# Quad_circuit_Dejun_Ryan.net
KiCad netlist of a schematic drawn in EAGLE
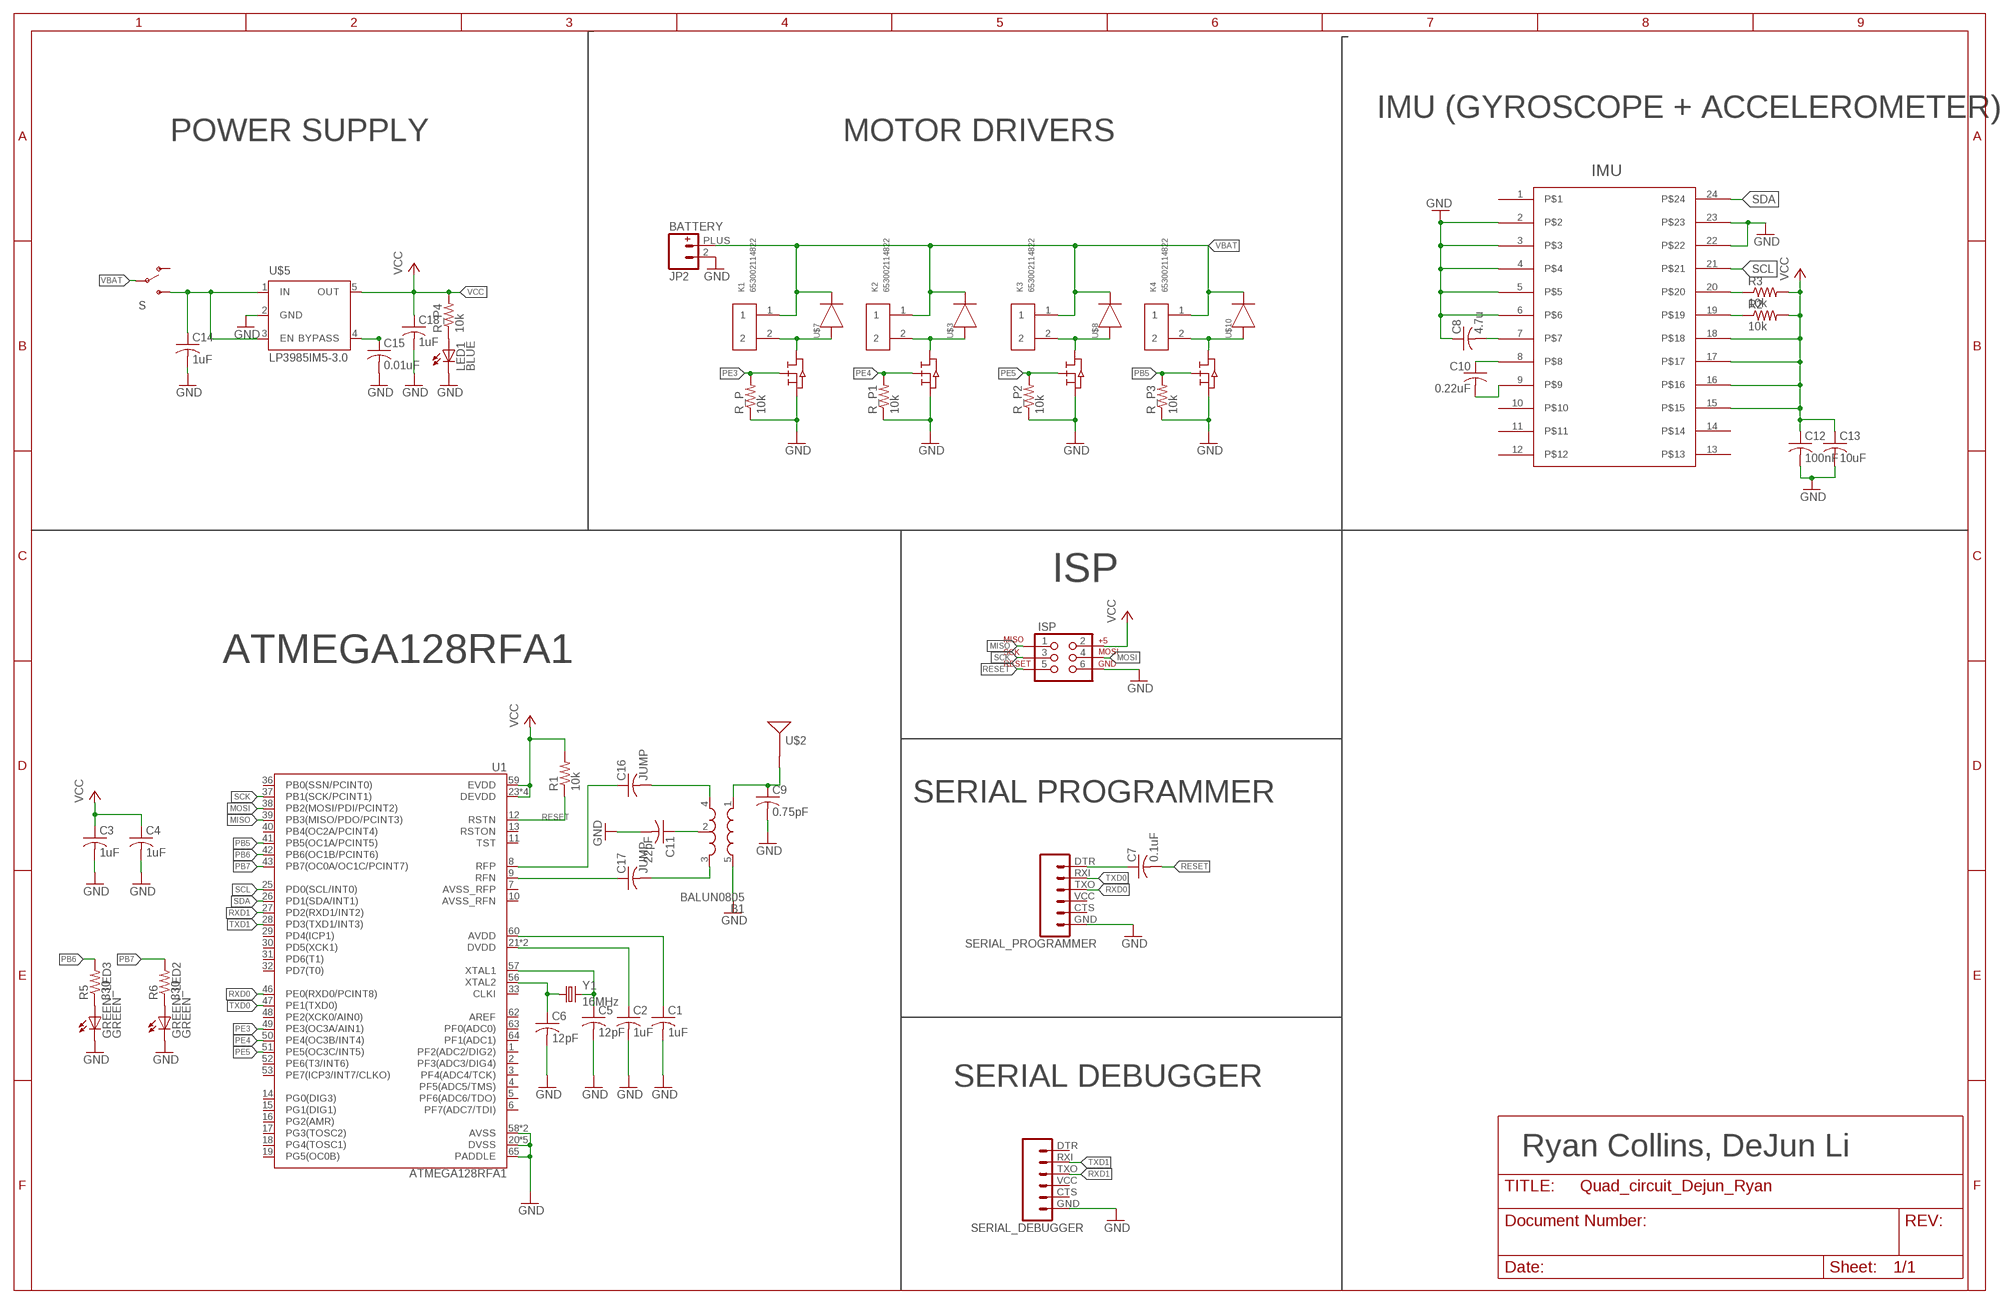
[diagram p0: schematic, sheet 1]

(export (version "E")
  (design (tool "Eeschema 10.0.6"))
  (components
    (comp (ref "B1")
      (value "BALUN0805")
      (footprint "eagle-import:BALUN")
      (libsource (lib "eagle-import") (part "BALUN0805"))
    )
    (comp (ref "C1")
      (value "1uF")
      (footprint "eagle-import:C0805")
      (libsource (lib "eagle-import") (part "C-USC0805"))
    )
    (comp (ref "C2")
      (value "1uF")
      (footprint "eagle-import:C0805")
      (libsource (lib "eagle-import") (part "C-USC0805"))
    )
    (comp (ref "C3")
      (value "1uF")
      (footprint "eagle-import:C0805")
      (libsource (lib "eagle-import") (part "C-USC0805"))
    )
    (comp (ref "C4")
      (value "1uF")
      (footprint "eagle-import:C0805")
      (libsource (lib "eagle-import") (part "C-USC0805"))
    )
    (comp (ref "C5")
      (value "12pF")
      (footprint "eagle-import:C0805")
      (libsource (lib "eagle-import") (part "C-USC0805"))
    )
    (comp (ref "C6")
      (value "12pF")
      (footprint "eagle-import:C0805")
      (libsource (lib "eagle-import") (part "C-USC0805"))
    )
    (comp (ref "C7")
      (value "0.1uF")
      (footprint "eagle-import:C0805")
      (libsource (lib "eagle-import") (part "C-USC0805"))
    )
    (comp (ref "C8")
      (value "4.7u")
      (footprint "eagle-import:C0805")
      (libsource (lib "eagle-import") (part "C-USC0805"))
    )
    (comp (ref "C9")
      (value "0.75pF")
      (footprint "eagle-import:C0805")
      (libsource (lib "eagle-import") (part "C-USC0805"))
    )
    (comp (ref "C10")
      (value "0.22uF")
      (footprint "eagle-import:C0805")
      (libsource (lib "eagle-import") (part "C-USC0805"))
    )
    (comp (ref "C11")
      (value "22pF")
      (footprint "eagle-import:C0805")
      (libsource (lib "eagle-import") (part "C-USC0805"))
    )
    (comp (ref "C12")
      (value "100nF")
      (footprint "eagle-import:C0805")
      (libsource (lib "eagle-import") (part "C-USC0805"))
    )
    (comp (ref "C13")
      (value "10uF")
      (footprint "eagle-import:C0805")
      (libsource (lib "eagle-import") (part "C-USC0805"))
    )
    (comp (ref "C14")
      (value "1uF")
      (footprint "eagle-import:C0805")
      (libsource (lib "eagle-import") (part "C-USC0805"))
    )
    (comp (ref "C15")
      (value "0.01uF")
      (footprint "eagle-import:C0805")
      (libsource (lib "eagle-import") (part "C-USC0805"))
    )
    (comp (ref "C16")
      (value "JUMP")
      (footprint "eagle-import:C0805")
      (libsource (lib "eagle-import") (part "C-USC0805"))
    )
    (comp (ref "C17")
      (value "JUMP")
      (footprint "eagle-import:C0805")
      (libsource (lib "eagle-import") (part "C-USC0805"))
    )
    (comp (ref "C18")
      (value "1uF")
      (footprint "eagle-import:C0805")
      (libsource (lib "eagle-import") (part "C-USC0805"))
    )
    (comp (ref "GREEN_LED2")
      (value "GREEN")
      (footprint "eagle-import:CHIP-LED0805")
      (libsource (lib "eagle-import") (part "LEDCHIP-LED0805"))
    )
    (comp (ref "GREEN_LED3")
      (value "GREEN")
      (footprint "eagle-import:CHIP-LED0805")
      (libsource (lib "eagle-import") (part "LEDCHIP-LED0805"))
    )
    (comp (ref "IMU")
      (value "IMU_LSM9DS0")
      (footprint "eagle-import:IMU_LSM9DS0")
      (libsource (lib "eagle-import") (part "IMU_LSM9DS0"))
    )
    (comp (ref "ISP")
      (value "AVR_SPI_PRG_6NS")
      (footprint "eagle-import:2X3-NS")
      (libsource (lib "eagle-import") (part "AVR_SPI_PRG_6NS"))
    )
    (comp (ref "JP2")
      (value "BATTERY")
      (footprint "eagle-import:1X02")
      (libsource (lib "eagle-import") (part "M02PTH"))
    )
    (comp (ref "K1")
      (value "653002114822")
      (footprint "eagle-import:653002114822")
      (libsource (lib "eagle-import") (part "653002114822"))
    )
    (comp (ref "K2")
      (value "653002114822")
      (footprint "eagle-import:653002114822")
      (libsource (lib "eagle-import") (part "653002114822"))
    )
    (comp (ref "K3")
      (value "653002114822")
      (footprint "eagle-import:653002114822")
      (libsource (lib "eagle-import") (part "653002114822"))
    )
    (comp (ref "K4")
      (value "653002114822")
      (footprint "eagle-import:653002114822")
      (libsource (lib "eagle-import") (part "653002114822"))
    )
    (comp (ref "LED1")
      (value "BLUE")
      (footprint "eagle-import:CHIP-LED0805")
      (libsource (lib "eagle-import") (part "LEDCHIP-LED0805"))
    )
    (comp (ref "R1")
      (value "10k")
      (footprint "eagle-import:R0805")
      (libsource (lib "eagle-import") (part "R-US_R0805"))
    )
    (comp (ref "R2")
      (value "10k")
      (footprint "eagle-import:R0805")
      (libsource (lib "eagle-import") (part "R-US_R0805"))
    )
    (comp (ref "R3")
      (value "10k")
      (footprint "eagle-import:R0805")
      (libsource (lib "eagle-import") (part "R-US_R0805"))
    )
    (comp (ref "R5")
      (value "330")
      (footprint "eagle-import:R0805")
      (libsource (lib "eagle-import") (part "R-US_R0805"))
    )
    (comp (ref "R6")
      (value "330")
      (footprint "eagle-import:R0805")
      (libsource (lib "eagle-import") (part "R-US_R0805"))
    )
    (comp (ref "R_P")
      (value "10k")
      (footprint "eagle-import:R0805")
      (libsource (lib "eagle-import") (part "R-US_R0805"))
    )
    (comp (ref "R_P1")
      (value "10k")
      (footprint "eagle-import:R0805")
      (libsource (lib "eagle-import") (part "R-US_R0805"))
    )
    (comp (ref "R_P2")
      (value "10k")
      (footprint "eagle-import:R0805")
      (libsource (lib "eagle-import") (part "R-US_R0805"))
    )
    (comp (ref "R_P3")
      (value "10k")
      (footprint "eagle-import:R0805")
      (libsource (lib "eagle-import") (part "R-US_R0805"))
    )
    (comp (ref "R_P4")
      (value "10k")
      (footprint "eagle-import:R0805")
      (libsource (lib "eagle-import") (part "R-US_R0805"))
    )
    (comp (ref "S")
      (value "WEEEEEE")
      (footprint "eagle-import:SWITCH-SPDT")
      (libsource (lib "eagle-import") (part "SWITCH-SPDTPTH"))
    )
    (comp (ref "SERIAL_DEBUGGER")
      (value "FTDI_BASICPTH")
      (footprint "eagle-import:FTDI_BASIC")
      (libsource (lib "eagle-import") (part "FTDI_BASICPTH"))
    )
    (comp (ref "SERIAL_PROGRAMMER")
      (value "FTDI_BASICPTH")
      (footprint "eagle-import:FTDI_BASIC")
      (libsource (lib "eagle-import") (part "FTDI_BASICPTH"))
    )
    (comp (ref "U$1")
      (value "MOSFET-SI2302CDS")
      (footprint "eagle-import:MOSFET-SI2302CDS")
      (fields (field (name "CREATOR") "DEJUN"))
      (libsource (lib "eagle-import") (part "MOSFET-SI2302CDS"))
    )
    (comp (ref "U$2")
      (value "ANTENNA2SMD5")
      (footprint "eagle-import:ANTENNA-CHIP5")
      (libsource (lib "eagle-import") (part "ANTENNA2SMD5"))
    )
    (comp (ref "U$3")
      (value "DIODE")
      (footprint "eagle-import:DIODE-BAS16WS")
      (fields (field (name "CREATOR") "DEJUN"))
      (libsource (lib "eagle-import") (part "DIODE-BAS16WS"))
    )
    (comp (ref "U$4")
      (value "MOSFET-SI2302CDS")
      (footprint "eagle-import:MOSFET-SI2302CDS")
      (fields (field (name "CREATOR") "DEJUN"))
      (libsource (lib "eagle-import") (part "MOSFET-SI2302CDS"))
    )
    (comp (ref "U$5")
      (value "LP3985IM5-3.0")
      (footprint "eagle-import:SOT23-DBV")
      (libsource (lib "eagle-import") (part "LP3985IM5-3.0"))
    )
    (comp (ref "U$6")
      (value "MOSFET-SI2302CDS")
      (footprint "eagle-import:MOSFET-SI2302CDS")
      (fields (field (name "CREATOR") "DEJUN"))
      (libsource (lib "eagle-import") (part "MOSFET-SI2302CDS"))
    )
    (comp (ref "U$7")
      (value "DIODE")
      (footprint "eagle-import:DIODE-BAS16WS")
      (fields (field (name "CREATOR") "DEJUN"))
      (libsource (lib "eagle-import") (part "DIODE-BAS16WS"))
    )
    (comp (ref "U$8")
      (value "DIODE")
      (footprint "eagle-import:DIODE-BAS16WS")
      (fields (field (name "CREATOR") "DEJUN"))
      (libsource (lib "eagle-import") (part "DIODE-BAS16WS"))
    )
    (comp (ref "U$9")
      (value "MOSFET-SI2302CDS")
      (footprint "eagle-import:MOSFET-SI2302CDS")
      (fields (field (name "CREATOR") "DEJUN"))
      (libsource (lib "eagle-import") (part "MOSFET-SI2302CDS"))
    )
    (comp (ref "U$10")
      (value "DIODE")
      (footprint "eagle-import:DIODE-BAS16WS")
      (fields (field (name "CREATOR") "DEJUN"))
      (libsource (lib "eagle-import") (part "DIODE-BAS16WS"))
    )
    (comp (ref "U1")
      (value "ATMEGA128RFA1")
      (footprint "eagle-import:QFN-64")
      (libsource (lib "eagle-import") (part "ATMEGA128RFA1"))
    )
    (comp (ref "Y1")
      (value "16MHz")
      (footprint "eagle-import:CRYSTAL-SMD-5X3")
      (libsource (lib "eagle-import") (part "CRYSTAL5X3"))
    )
  )
  (nets
    (net (code "1") (name "GND") (class "Default")
      (node (ref "B1") (pin "5") (pinfunction "GND_5") (pintype "bidirectional"))
      (node (ref "C1") (pin "2") (pinfunction "2_2") (pintype "passive"))
      (node (ref "C11") (pin "2") (pinfunction "2_2") (pintype "passive"))
      (node (ref "C12") (pin "2") (pinfunction "2_2") (pintype "passive"))
      (node (ref "C13") (pin "2") (pinfunction "2_2") (pintype "passive"))
      (node (ref "C14") (pin "2") (pinfunction "2_2") (pintype "passive"))
      (node (ref "C15") (pin "2") (pinfunction "2_2") (pintype "passive"))
      (node (ref "C18") (pin "2") (pinfunction "2_2") (pintype "passive"))
      (node (ref "C2") (pin "2") (pinfunction "2_2") (pintype "passive"))
      (node (ref "C3") (pin "2") (pinfunction "2_2") (pintype "passive"))
      (node (ref "C4") (pin "2") (pinfunction "2_2") (pintype "passive"))
      (node (ref "C5") (pin "2") (pinfunction "2_2") (pintype "passive"))
      (node (ref "C6") (pin "2") (pinfunction "2_2") (pintype "passive"))
      (node (ref "C8") (pin "1") (pinfunction "1_1") (pintype "passive"))
      (node (ref "C9") (pin "2") (pinfunction "2_2") (pintype "passive"))
      (node (ref "GREEN_LED2") (pin "C") (pinfunction "C_C") (pintype "passive"))
      (node (ref "GREEN_LED3") (pin "C") (pinfunction "C_C") (pintype "passive"))
      (node (ref "IMU") (pin "2") (pinfunction "P$2_2") (pintype "bidirectional"))
      (node (ref "IMU") (pin "22") (pinfunction "P$22_22") (pintype "bidirectional"))
      (node (ref "IMU") (pin "23") (pinfunction "P$23_23") (pintype "bidirectional"))
      (node (ref "IMU") (pin "3") (pinfunction "P$3_3") (pintype "bidirectional"))
      (node (ref "IMU") (pin "4") (pinfunction "P$4_4") (pintype "bidirectional"))
      (node (ref "IMU") (pin "5") (pinfunction "P$5_5") (pintype "bidirectional"))
      (node (ref "IMU") (pin "6") (pinfunction "P$6_6") (pintype "bidirectional"))
      (node (ref "ISP") (pin "6") (pinfunction "6_6") (pintype "passive"))
      (node (ref "JP2") (pin "2") (pinfunction "2_2") (pintype "passive"))
      (node (ref "LED1") (pin "C") (pinfunction "C_C") (pintype "passive"))
      (node (ref "R_P") (pin "1") (pinfunction "1_1") (pintype "passive"))
      (node (ref "R_P1") (pin "1") (pinfunction "1_1") (pintype "passive"))
      (node (ref "R_P2") (pin "1") (pinfunction "1_1") (pintype "passive"))
      (node (ref "R_P3") (pin "1") (pinfunction "1_1") (pintype "passive"))
      (node (ref "SERIAL_DEBUGGER") (pin "GND") (pinfunction "6_GND") (pintype "passive"))
      (node (ref "SERIAL_PROGRAMMER") (pin "GND") (pinfunction "6_GND") (pintype "passive"))
      (node (ref "U$1") (pin "SOURCE") (pinfunction "S_SOURCE") (pintype "bidirectional"))
      (node (ref "U$4") (pin "SOURCE") (pinfunction "S_SOURCE") (pintype "bidirectional"))
      (node (ref "U$5") (pin "2") (pinfunction "GND_2") (pintype "input"))
      (node (ref "U$6") (pin "SOURCE") (pinfunction "S_SOURCE") (pintype "bidirectional"))
      (node (ref "U$9") (pin "SOURCE") (pinfunction "S_SOURCE") (pintype "bidirectional"))
      (node (ref "U1") (pin "20") (pinfunction "DVSS_20") (pintype "bidirectional"))
      (node (ref "U1") (pin "24") (pinfunction "DVSS_24") (pintype "bidirectional"))
      (node (ref "U1") (pin "35") (pinfunction "DVSS_35") (pintype "bidirectional"))
      (node (ref "U1") (pin "45") (pinfunction "DVSS_45") (pintype "bidirectional"))
      (node (ref "U1") (pin "55") (pinfunction "DVSS_55") (pintype "bidirectional"))
      (node (ref "U1") (pin "58") (pinfunction "AVSS_58") (pintype "bidirectional"))
      (node (ref "U1") (pin "61") (pinfunction "AVSS_61") (pintype "bidirectional"))
      (node (ref "U1") (pin "65") (pinfunction "PADDLE_65") (pintype "bidirectional"))
    )
    (net (code "2") (name "MISO") (class "Default")
      (node (ref "ISP") (pin "1") (pinfunction "1_1") (pintype "passive"))
      (node (ref "U1") (pin "39") (pinfunction "PB3(MISO/PDO/PCINT3)_39") (pintype "bidirectional"))
    )
    (net (code "3") (name "MOSI") (class "Default")
      (node (ref "ISP") (pin "4") (pinfunction "4_4") (pintype "passive"))
      (node (ref "U1") (pin "38") (pinfunction "PB2(MOSI/PDI/PCINT2)_38") (pintype "bidirectional"))
    )
    (net (code "4") (name "Net-(B1-GND-Pad2)") (class "Default")
      (node (ref "B1") (pin "2") (pinfunction "GND_2") (pintype "bidirectional"))
      (node (ref "C11") (pin "1") (pinfunction "1_1") (pintype "passive"))
    )
    (net (code "5") (name "Net-(B1-IN)") (class "Default")
      (node (ref "B1") (pin "1") (pinfunction "IN_1") (pintype "bidirectional"))
      (node (ref "C9") (pin "1") (pinfunction "1_1") (pintype "passive"))
      (node (ref "U$2") (pin "FEED") (pinfunction "SIGNAL_FEED") (pintype "bidirectional"))
    )
    (net (code "6") (name "Net-(B1-OUT1)") (class "Default")
      (node (ref "B1") (pin "4") (pinfunction "OUT1_4") (pintype "bidirectional"))
      (node (ref "C16") (pin "2") (pinfunction "2_2") (pintype "passive"))
    )
    (net (code "7") (name "Net-(B1-OUT2)") (class "Default")
      (node (ref "B1") (pin "3") (pinfunction "OUT2_3") (pintype "bidirectional"))
      (node (ref "C17") (pin "2") (pinfunction "2_2") (pintype "passive"))
    )
    (net (code "8") (name "Net-(C2-Pad1)") (class "Default")
      (node (ref "C2") (pin "1") (pinfunction "1_1") (pintype "passive"))
      (node (ref "U1") (pin "21") (pinfunction "DVDD_21") (pintype "bidirectional"))
      (node (ref "U1") (pin "22") (pinfunction "DVDD_22") (pintype "bidirectional"))
    )
    (net (code "9") (name "Net-(GREEN_LED2-PadA)") (class "Default")
      (node (ref "GREEN_LED2") (pin "A") (pinfunction "A_A") (pintype "passive"))
      (node (ref "R6") (pin "1") (pinfunction "1_1") (pintype "passive"))
    )
    (net (code "10") (name "Net-(GREEN_LED3-PadA)") (class "Default")
      (node (ref "GREEN_LED3") (pin "A") (pinfunction "A_A") (pintype "passive"))
      (node (ref "R5") (pin "1") (pinfunction "1_1") (pintype "passive"))
    )
    (net (code "11") (name "Net-(IMU-P$7)") (class "Default")
      (node (ref "C8") (pin "2") (pinfunction "2_2") (pintype "passive"))
      (node (ref "IMU") (pin "7") (pinfunction "P$7_7") (pintype "bidirectional"))
    )
    (net (code "12") (name "Net-(IMU-P$8)") (class "Default")
      (node (ref "C10") (pin "1") (pinfunction "1_1") (pintype "passive"))
      (node (ref "IMU") (pin "8") (pinfunction "P$8_8") (pintype "bidirectional"))
    )
    (net (code "13") (name "Net-(IMU-P$9)") (class "Default")
      (node (ref "C10") (pin "2") (pinfunction "2_2") (pintype "passive"))
      (node (ref "IMU") (pin "9") (pinfunction "P$9_9") (pintype "bidirectional"))
    )
    (net (code "14") (name "Net-(IMU-P$19)") (class "Default")
      (node (ref "IMU") (pin "19") (pinfunction "P$19_19") (pintype "bidirectional"))
      (node (ref "R2") (pin "1") (pinfunction "1_1") (pintype "passive"))
    )
    (net (code "15") (name "Net-(IMU-P$20)") (class "Default")
      (node (ref "IMU") (pin "20") (pinfunction "P$20_20") (pintype "bidirectional"))
      (node (ref "R3") (pin "1") (pinfunction "1_1") (pintype "passive"))
    )
    (net (code "16") (name "Net-(LED1-PadA)") (class "Default")
      (node (ref "LED1") (pin "A") (pinfunction "A_A") (pintype "passive"))
      (node (ref "R_P4") (pin "1") (pinfunction "1_1") (pintype "passive"))
    )
    (net (code "17") (name "Net-(S-S)") (class "Default")
      (node (ref "C14") (pin "1") (pinfunction "1_1") (pintype "passive"))
      (node (ref "S") (pin "3") (pinfunction "S_3") (pintype "passive"))
      (node (ref "U$5") (pin "1") (pinfunction "IN_1") (pintype "input"))
      (node (ref "U$5") (pin "3") (pinfunction "EN_3") (pintype "input"))
    )
    (net (code "18") (name "Net-(SERIAL_PROGRAMMER-1)") (class "Default")
      (node (ref "C7") (pin "1") (pinfunction "1_1") (pintype "passive"))
      (node (ref "SERIAL_PROGRAMMER") (pin "DTR") (pinfunction "1_DTR") (pintype "passive"))
    )
    (net (code "19") (name "Net-(U$1-D)") (class "Default")
      (node (ref "K2") (pin "2") (pinfunction "2_2") (pintype "bidirectional"))
      (node (ref "U$1") (pin "DRAIN") (pinfunction "D_DRAIN") (pintype "bidirectional"))
      (node (ref "U$3") (pin "ANODE") (pinfunction "A_ANODE") (pintype "bidirectional"))
    )
    (net (code "20") (name "Net-(U$4-D)") (class "Default")
      (node (ref "K3") (pin "2") (pinfunction "2_2") (pintype "bidirectional"))
      (node (ref "U$4") (pin "DRAIN") (pinfunction "D_DRAIN") (pintype "bidirectional"))
      (node (ref "U$8") (pin "ANODE") (pinfunction "A_ANODE") (pintype "bidirectional"))
    )
    (net (code "21") (name "Net-(U$5-BYPASS)") (class "Default")
      (node (ref "C15") (pin "1") (pinfunction "1_1") (pintype "passive"))
      (node (ref "U$5") (pin "4") (pinfunction "BYPASS_4") (pintype "passive"))
    )
    (net (code "22") (name "Net-(U$6-D)") (class "Default")
      (node (ref "K1") (pin "2") (pinfunction "2_2") (pintype "bidirectional"))
      (node (ref "U$6") (pin "DRAIN") (pinfunction "D_DRAIN") (pintype "bidirectional"))
      (node (ref "U$7") (pin "ANODE") (pinfunction "A_ANODE") (pintype "bidirectional"))
    )
    (net (code "23") (name "Net-(U$10-A)") (class "Default")
      (node (ref "K4") (pin "2") (pinfunction "2_2") (pintype "bidirectional"))
      (node (ref "U$10") (pin "ANODE") (pinfunction "A_ANODE") (pintype "bidirectional"))
      (node (ref "U$9") (pin "DRAIN") (pinfunction "D_DRAIN") (pintype "bidirectional"))
    )
    (net (code "24") (name "Net-(U1-AVDD)") (class "Default")
      (node (ref "C1") (pin "1") (pinfunction "1_1") (pintype "passive"))
      (node (ref "U1") (pin "60") (pinfunction "AVDD_60") (pintype "bidirectional"))
    )
    (net (code "25") (name "Net-(U1-RFN)") (class "Default")
      (node (ref "C17") (pin "1") (pinfunction "1_1") (pintype "passive"))
      (node (ref "U1") (pin "9") (pinfunction "RFN_9") (pintype "bidirectional"))
    )
    (net (code "26") (name "Net-(U1-RFP)") (class "Default")
      (node (ref "C16") (pin "1") (pinfunction "1_1") (pintype "passive"))
      (node (ref "U1") (pin "8") (pinfunction "RFP_8") (pintype "bidirectional"))
    )
    (net (code "27") (name "Net-(U1-XTAL1)") (class "Default")
      (node (ref "C5") (pin "1") (pinfunction "1_1") (pintype "passive"))
      (node (ref "U1") (pin "57") (pinfunction "XTAL1_57") (pintype "bidirectional"))
      (node (ref "Y1") (pin "3") (pinfunction "2_3") (pintype "passive"))
    )
    (net (code "28") (name "Net-(U1-XTAL2)") (class "Default")
      (node (ref "C6") (pin "1") (pinfunction "1_1") (pintype "passive"))
      (node (ref "U1") (pin "56") (pinfunction "XTAL2_56") (pintype "bidirectional"))
      (node (ref "Y1") (pin "1") (pinfunction "1_1") (pintype "passive"))
    )
    (net (code "29") (name "PB5") (class "Default")
      (node (ref "R_P3") (pin "2") (pinfunction "2_2") (pintype "passive"))
      (node (ref "U$9") (pin "GATE") (pinfunction "G_GATE") (pintype "bidirectional"))
      (node (ref "U1") (pin "41") (pinfunction "PB5(OC1A/PCINT5)_41") (pintype "bidirectional"))
    )
    (net (code "30") (name "PB6") (class "Default")
      (node (ref "R5") (pin "2") (pinfunction "2_2") (pintype "passive"))
      (node (ref "U1") (pin "42") (pinfunction "PB6(OC1B/PCINT6)_42") (pintype "bidirectional"))
    )
    (net (code "31") (name "PB7") (class "Default")
      (node (ref "R6") (pin "2") (pinfunction "2_2") (pintype "passive"))
      (node (ref "U1") (pin "43") (pinfunction "PB7(OC0A/OC1C/PCINT7)_43") (pintype "bidirectional"))
    )
    (net (code "32") (name "PE3") (class "Default")
      (node (ref "R_P") (pin "2") (pinfunction "2_2") (pintype "passive"))
      (node (ref "U$6") (pin "GATE") (pinfunction "G_GATE") (pintype "bidirectional"))
      (node (ref "U1") (pin "49") (pinfunction "PE3(OC3A/AIN1)_49") (pintype "bidirectional"))
    )
    (net (code "33") (name "PE4") (class "Default")
      (node (ref "R_P1") (pin "2") (pinfunction "2_2") (pintype "passive"))
      (node (ref "U$1") (pin "GATE") (pinfunction "G_GATE") (pintype "bidirectional"))
      (node (ref "U1") (pin "50") (pinfunction "PE4(OC3B/INT4)_50") (pintype "bidirectional"))
    )
    (net (code "34") (name "PE5") (class "Default")
      (node (ref "R_P2") (pin "2") (pinfunction "2_2") (pintype "passive"))
      (node (ref "U$4") (pin "GATE") (pinfunction "G_GATE") (pintype "bidirectional"))
      (node (ref "U1") (pin "51") (pinfunction "PE5(OC3C/INT5)_51") (pintype "bidirectional"))
    )
    (net (code "35") (name "RESET") (class "Default")
      (node (ref "C7") (pin "2") (pinfunction "2_2") (pintype "passive"))
      (node (ref "ISP") (pin "5") (pinfunction "5_5") (pintype "passive"))
      (node (ref "R1") (pin "1") (pinfunction "1_1") (pintype "passive"))
      (node (ref "U1") (pin "12") (pinfunction "RSTN_12") (pintype "bidirectional"))
    )
    (net (code "36") (name "RXD0") (class "Default")
      (node (ref "SERIAL_PROGRAMMER") (pin "TXO") (pinfunction "3_TXO") (pintype "passive"))
      (node (ref "U1") (pin "46") (pinfunction "PE0(RXD0/PCINT8)_46") (pintype "bidirectional"))
    )
    (net (code "37") (name "RXD1") (class "Default")
      (node (ref "SERIAL_DEBUGGER") (pin "TXO") (pinfunction "3_TXO") (pintype "passive"))
      (node (ref "U1") (pin "27") (pinfunction "PD2(RXD1/INT2)_27") (pintype "bidirectional"))
    )
    (net (code "38") (name "SCK") (class "Default")
      (node (ref "ISP") (pin "3") (pinfunction "3_3") (pintype "passive"))
      (node (ref "U1") (pin "37") (pinfunction "PB1(SCK/PCINT1)_37") (pintype "bidirectional"))
    )
    (net (code "39") (name "SCL") (class "Default")
      (node (ref "IMU") (pin "21") (pinfunction "P$21_21") (pintype "bidirectional"))
      (node (ref "U1") (pin "25") (pinfunction "PD0(SCL/INT0)_25") (pintype "bidirectional"))
    )
    (net (code "40") (name "SDA") (class "Default")
      (node (ref "IMU") (pin "24") (pinfunction "P$24_24") (pintype "bidirectional"))
      (node (ref "U1") (pin "26") (pinfunction "PD1(SDA/INT1)_26") (pintype "bidirectional"))
    )
    (net (code "41") (name "TXD0") (class "Default")
      (node (ref "SERIAL_PROGRAMMER") (pin "RXI") (pinfunction "2_RXI") (pintype "passive"))
      (node (ref "U1") (pin "47") (pinfunction "PE1(TXD0)_47") (pintype "bidirectional"))
    )
    (net (code "42") (name "TXD1") (class "Default")
      (node (ref "SERIAL_DEBUGGER") (pin "RXI") (pinfunction "2_RXI") (pintype "passive"))
      (node (ref "U1") (pin "28") (pinfunction "PD3(TXD1/INT3)_28") (pintype "bidirectional"))
    )
    (net (code "43") (name "VBAT") (class "Default")
      (node (ref "JP2") (pin "PLUS") (pinfunction "PLUS_PLUS") (pintype "passive"))
      (node (ref "K1") (pin "1") (pinfunction "1_1") (pintype "bidirectional"))
      (node (ref "K2") (pin "1") (pinfunction "1_1") (pintype "bidirectional"))
      (node (ref "K3") (pin "1") (pinfunction "1_1") (pintype "bidirectional"))
      (node (ref "K4") (pin "1") (pinfunction "1_1") (pintype "bidirectional"))
      (node (ref "S") (pin "2") (pinfunction "P_2") (pintype "passive"))
      (node (ref "U$10") (pin "CATHODE") (pinfunction "C_CATHODE") (pintype "bidirectional"))
      (node (ref "U$3") (pin "CATHODE") (pinfunction "C_CATHODE") (pintype "bidirectional"))
      (node (ref "U$7") (pin "CATHODE") (pinfunction "C_CATHODE") (pintype "bidirectional"))
      (node (ref "U$8") (pin "CATHODE") (pinfunction "C_CATHODE") (pintype "bidirectional"))
    )
    (net (code "44") (name "VCC") (class "Default")
      (node (ref "C12") (pin "1") (pinfunction "1_1") (pintype "passive"))
      (node (ref "C13") (pin "1") (pinfunction "1_1") (pintype "passive"))
      (node (ref "C18") (pin "1") (pinfunction "1_1") (pintype "passive"))
      (node (ref "C3") (pin "1") (pinfunction "1_1") (pintype "passive"))
      (node (ref "C4") (pin "1") (pinfunction "1_1") (pintype "passive"))
      (node (ref "IMU") (pin "15") (pinfunction "P$15_15") (pintype "bidirectional"))
      (node (ref "IMU") (pin "16") (pinfunction "P$16_16") (pintype "bidirectional"))
      (node (ref "IMU") (pin "17") (pinfunction "P$17_17") (pintype "bidirectional"))
      (node (ref "IMU") (pin "18") (pinfunction "P$18_18") (pintype "bidirectional"))
      (node (ref "ISP") (pin "2") (pinfunction "2_2") (pintype "passive"))
      (node (ref "R1") (pin "2") (pinfunction "2_2") (pintype "passive"))
      (node (ref "R2") (pin "2") (pinfunction "2_2") (pintype "passive"))
      (node (ref "R3") (pin "2") (pinfunction "2_2") (pintype "passive"))
      (node (ref "R_P4") (pin "2") (pinfunction "2_2") (pintype "passive"))
      (node (ref "U$5") (pin "5") (pinfunction "OUT_5") (pintype "passive"))
      (node (ref "U1") (pin "23") (pinfunction "DEVDD_23") (pintype "bidirectional"))
      (node (ref "U1") (pin "34") (pinfunction "DEVDD_34") (pintype "bidirectional"))
      (node (ref "U1") (pin "44") (pinfunction "DEVDD_44") (pintype "bidirectional"))
      (node (ref "U1") (pin "54") (pinfunction "DEVDD_54") (pintype "bidirectional"))
      (node (ref "U1") (pin "59") (pinfunction "EVDD_59") (pintype "bidirectional"))
    )
    (net (code "45") (name "unconnected-(IMU-P$1-Pad1)") (class "Default")
      (node (ref "IMU") (pin "1") (pinfunction "P$1_1") (pintype "bidirectional"))
    )
    (net (code "46") (name "unconnected-(IMU-P$10-Pad10)") (class "Default")
      (node (ref "IMU") (pin "10") (pinfunction "P$10_10") (pintype "bidirectional"))
    )
    (net (code "47") (name "unconnected-(IMU-P$11-Pad11)") (class "Default")
      (node (ref "IMU") (pin "11") (pinfunction "P$11_11") (pintype "bidirectional"))
    )
    (net (code "48") (name "unconnected-(IMU-P$12-Pad12)") (class "Default")
      (node (ref "IMU") (pin "12") (pinfunction "P$12_12") (pintype "bidirectional"))
    )
    (net (code "49") (name "unconnected-(IMU-P$13-Pad13)") (class "Default")
      (node (ref "IMU") (pin "13") (pinfunction "P$13_13") (pintype "bidirectional"))
    )
    (net (code "50") (name "unconnected-(IMU-P$14-Pad14)") (class "Default")
      (node (ref "IMU") (pin "14") (pinfunction "P$14_14") (pintype "bidirectional"))
    )
    (net (code "51") (name "unconnected-(S-O-Pad1)") (class "Default")
      (node (ref "S") (pin "1") (pinfunction "O_1") (pintype "passive"))
    )
    (net (code "52") (name "unconnected-(SERIAL_DEBUGGER-1-PadDTR)") (class "Default")
      (node (ref "SERIAL_DEBUGGER") (pin "DTR") (pinfunction "1_DTR") (pintype "passive"))
    )
    (net (code "53") (name "unconnected-(SERIAL_DEBUGGER-4-PadVCC)") (class "Default")
      (node (ref "SERIAL_DEBUGGER") (pin "VCC") (pinfunction "4_VCC") (pintype "passive"))
    )
    (net (code "54") (name "unconnected-(SERIAL_DEBUGGER-5-PadCTS)") (class "Default")
      (node (ref "SERIAL_DEBUGGER") (pin "CTS") (pinfunction "5_CTS") (pintype "passive"))
    )
    (net (code "55") (name "unconnected-(SERIAL_PROGRAMMER-4-PadVCC)") (class "Default")
      (node (ref "SERIAL_PROGRAMMER") (pin "VCC") (pinfunction "4_VCC") (pintype "passive"))
    )
    (net (code "56") (name "unconnected-(SERIAL_PROGRAMMER-5-PadCTS)") (class "Default")
      (node (ref "SERIAL_PROGRAMMER") (pin "CTS") (pinfunction "5_CTS") (pintype "passive"))
    )
    (net (code "57") (name "unconnected-(U1-AREF-Pad62)") (class "Default")
      (node (ref "U1") (pin "62") (pinfunction "AREF_62") (pintype "bidirectional"))
    )
    (net (code "58") (name "unconnected-(U1-AVSS_RFN-Pad10)") (class "Default")
      (node (ref "U1") (pin "10") (pinfunction "AVSS_RFN_10") (pintype "bidirectional"))
    )
    (net (code "59") (name "unconnected-(U1-AVSS_RFP-Pad7)") (class "Default")
      (node (ref "U1") (pin "7") (pinfunction "AVSS_RFP_7") (pintype "bidirectional"))
    )
    (net (code "60") (name "unconnected-(U1-CLKI-Pad33)") (class "Default")
      (node (ref "U1") (pin "33") (pinfunction "CLKI_33") (pintype "bidirectional"))
    )
    (net (code "61") (name "unconnected-(U1-PB0(SSN{slash}PCINT0)-Pad36)") (class "Default")
      (node (ref "U1") (pin "36") (pinfunction "PB0(SSN/PCINT0)_36") (pintype "bidirectional"))
    )
    (net (code "62") (name "unconnected-(U1-PB4(OC2A{slash}PCINT4)-Pad40)") (class "Default")
      (node (ref "U1") (pin "40") (pinfunction "PB4(OC2A/PCINT4)_40") (pintype "bidirectional"))
    )
    (net (code "63") (name "unconnected-(U1-PD4(ICP1)-Pad29)") (class "Default")
      (node (ref "U1") (pin "29") (pinfunction "PD4(ICP1)_29") (pintype "bidirectional"))
    )
    (net (code "64") (name "unconnected-(U1-PD5(XCK1)-Pad30)") (class "Default")
      (node (ref "U1") (pin "30") (pinfunction "PD5(XCK1)_30") (pintype "bidirectional"))
    )
    (net (code "65") (name "unconnected-(U1-PD6(T1)-Pad31)") (class "Default")
      (node (ref "U1") (pin "31") (pinfunction "PD6(T1)_31") (pintype "bidirectional"))
    )
    (net (code "66") (name "unconnected-(U1-PD7(T0)-Pad32)") (class "Default")
      (node (ref "U1") (pin "32") (pinfunction "PD7(T0)_32") (pintype "bidirectional"))
    )
    (net (code "67") (name "unconnected-(U1-PE2(XCK0{slash}AIN0)-Pad48)") (class "Default")
      (node (ref "U1") (pin "48") (pinfunction "PE2(XCK0/AIN0)_48") (pintype "bidirectional"))
    )
    (net (code "68") (name "unconnected-(U1-PE6(T3{slash}INT6)-Pad52)") (class "Default")
      (node (ref "U1") (pin "52") (pinfunction "PE6(T3/INT6)_52") (pintype "bidirectional"))
    )
    (net (code "69") (name "unconnected-(U1-PE7(ICP3{slash}INT7{slash}CLKO)-Pad53)") (class "Default")
      (node (ref "U1") (pin "53") (pinfunction "PE7(ICP3/INT7/CLKO)_53") (pintype "bidirectional"))
    )
    (net (code "70") (name "unconnected-(U1-PF0(ADC0)-Pad63)") (class "Default")
      (node (ref "U1") (pin "63") (pinfunction "PF0(ADC0)_63") (pintype "bidirectional"))
    )
    (net (code "71") (name "unconnected-(U1-PF1(ADC1)-Pad64)") (class "Default")
      (node (ref "U1") (pin "64") (pinfunction "PF1(ADC1)_64") (pintype "bidirectional"))
    )
    (net (code "72") (name "unconnected-(U1-PF2(ADC2{slash}DIG2)-Pad1)") (class "Default")
      (node (ref "U1") (pin "1") (pinfunction "PF2(ADC2/DIG2)_1") (pintype "bidirectional"))
    )
    (net (code "73") (name "unconnected-(U1-PF3(ADC3{slash}DIG4)-Pad2)") (class "Default")
      (node (ref "U1") (pin "2") (pinfunction "PF3(ADC3/DIG4)_2") (pintype "bidirectional"))
    )
    (net (code "74") (name "unconnected-(U1-PF4(ADC4{slash}TCK)-Pad3)") (class "Default")
      (node (ref "U1") (pin "3") (pinfunction "PF4(ADC4/TCK)_3") (pintype "bidirectional"))
    )
    (net (code "75") (name "unconnected-(U1-PF5(ADC5{slash}TMS)-Pad4)") (class "Default")
      (node (ref "U1") (pin "4") (pinfunction "PF5(ADC5/TMS)_4") (pintype "bidirectional"))
    )
    (net (code "76") (name "unconnected-(U1-PF6(ADC6{slash}TDO)-Pad5)") (class "Default")
      (node (ref "U1") (pin "5") (pinfunction "PF6(ADC6/TDO)_5") (pintype "bidirectional"))
    )
    (net (code "77") (name "unconnected-(U1-PF7(ADC7{slash}TDI)-Pad6)") (class "Default")
      (node (ref "U1") (pin "6") (pinfunction "PF7(ADC7/TDI)_6") (pintype "bidirectional"))
    )
    (net (code "78") (name "unconnected-(U1-PG0(DIG3)-Pad14)") (class "Default")
      (node (ref "U1") (pin "14") (pinfunction "PG0(DIG3)_14") (pintype "bidirectional"))
    )
    (net (code "79") (name "unconnected-(U1-PG1(DIG1)-Pad15)") (class "Default")
      (node (ref "U1") (pin "15") (pinfunction "PG1(DIG1)_15") (pintype "bidirectional"))
    )
    (net (code "80") (name "unconnected-(U1-PG2(AMR)-Pad16)") (class "Default")
      (node (ref "U1") (pin "16") (pinfunction "PG2(AMR)_16") (pintype "bidirectional"))
    )
    (net (code "81") (name "unconnected-(U1-PG3(TOSC2)-Pad17)") (class "Default")
      (node (ref "U1") (pin "17") (pinfunction "PG3(TOSC2)_17") (pintype "bidirectional"))
    )
    (net (code "82") (name "unconnected-(U1-PG4(TOSC1)-Pad18)") (class "Default")
      (node (ref "U1") (pin "18") (pinfunction "PG4(TOSC1)_18") (pintype "bidirectional"))
    )
    (net (code "83") (name "unconnected-(U1-PG5(OC0B)-Pad19)") (class "Default")
      (node (ref "U1") (pin "19") (pinfunction "PG5(OC0B)_19") (pintype "bidirectional"))
    )
    (net (code "84") (name "unconnected-(U1-RSTON-Pad13)") (class "Default")
      (node (ref "U1") (pin "13") (pinfunction "RSTON_13") (pintype "bidirectional"))
    )
    (net (code "85") (name "unconnected-(U1-TST-Pad11)") (class "Default")
      (node (ref "U1") (pin "11") (pinfunction "TST_11") (pintype "bidirectional"))
    )
  )
)
